# 74HC595.net
KiCad netlist of a schematic drawn in Altium Designer
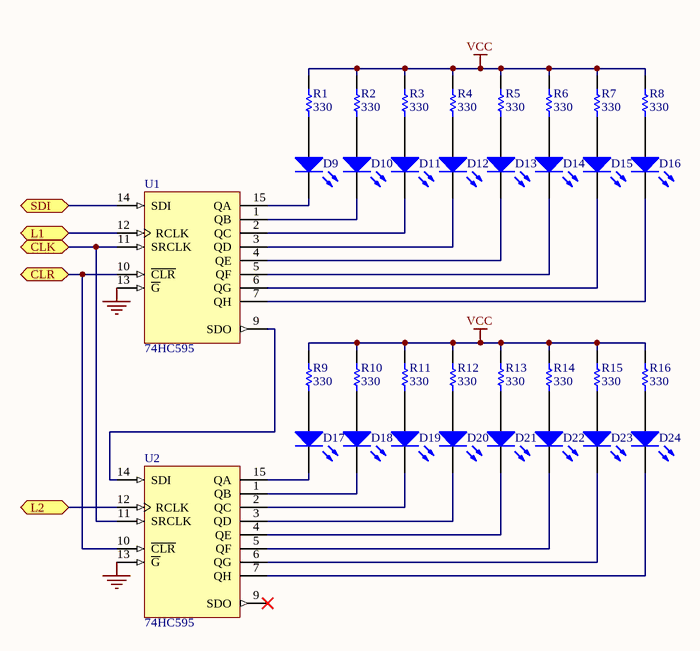
[diagram p0: 74HC595.SchDoc]

(export (version "E")
  (design (tool "Eeschema 10.0.6"))
  (components
    (comp (ref "D9")
      (value "LED0")
      (footprint "CAPPR2-5X6.8")
      (description "Typical INFRARED GaAs LED")
      (fields (field (name "PUBLISHER") "Altium Limited"))
      (libsource (lib "Miscellaneous Devices") (part "LED0"))
    )
    (comp (ref "D10")
      (value "LED0")
      (footprint "CAPPR2-5X6.8")
      (description "Typical INFRARED GaAs LED")
      (fields (field (name "PUBLISHER") "Altium Limited"))
      (libsource (lib "Miscellaneous Devices") (part "LED0"))
    )
    (comp (ref "D11")
      (value "LED0")
      (footprint "CAPPR2-5X6.8")
      (description "Typical INFRARED GaAs LED")
      (fields (field (name "PUBLISHER") "Altium Limited"))
      (libsource (lib "Miscellaneous Devices") (part "LED0"))
    )
    (comp (ref "D12")
      (value "LED0")
      (footprint "CAPPR2-5X6.8")
      (description "Typical INFRARED GaAs LED")
      (fields (field (name "PUBLISHER") "Altium Limited"))
      (libsource (lib "Miscellaneous Devices") (part "LED0"))
    )
    (comp (ref "D13")
      (value "LED0")
      (footprint "CAPPR2-5X6.8")
      (description "Typical INFRARED GaAs LED")
      (fields (field (name "PUBLISHER") "Altium Limited"))
      (libsource (lib "Miscellaneous Devices") (part "LED0"))
    )
    (comp (ref "D14")
      (value "LED0")
      (footprint "CAPPR2-5X6.8")
      (description "Typical INFRARED GaAs LED")
      (fields (field (name "PUBLISHER") "Altium Limited"))
      (libsource (lib "Miscellaneous Devices") (part "LED0"))
    )
    (comp (ref "D15")
      (value "LED0")
      (footprint "CAPPR2-5X6.8")
      (description "Typical INFRARED GaAs LED")
      (fields (field (name "PUBLISHER") "Altium Limited"))
      (libsource (lib "Miscellaneous Devices") (part "LED0"))
    )
    (comp (ref "D16")
      (value "LED0")
      (footprint "CAPPR2-5X6.8")
      (description "Typical INFRARED GaAs LED")
      (fields (field (name "PUBLISHER") "Altium Limited"))
      (libsource (lib "Miscellaneous Devices") (part "LED0"))
    )
    (comp (ref "D17")
      (value "LED0")
      (footprint "CAPPR2-5X6.8")
      (description "Typical INFRARED GaAs LED")
      (fields (field (name "PUBLISHER") "Altium Limited"))
      (libsource (lib "Miscellaneous Devices") (part "LED0"))
    )
    (comp (ref "D18")
      (value "LED0")
      (footprint "CAPPR2-5X6.8")
      (description "Typical INFRARED GaAs LED")
      (fields (field (name "PUBLISHER") "Altium Limited"))
      (libsource (lib "Miscellaneous Devices") (part "LED0"))
    )
    (comp (ref "D19")
      (value "LED0")
      (footprint "CAPPR2-5X6.8")
      (description "Typical INFRARED GaAs LED")
      (fields (field (name "PUBLISHER") "Altium Limited"))
      (libsource (lib "Miscellaneous Devices") (part "LED0"))
    )
    (comp (ref "D20")
      (value "LED0")
      (footprint "CAPPR2-5X6.8")
      (description "Typical INFRARED GaAs LED")
      (fields (field (name "PUBLISHER") "Altium Limited"))
      (libsource (lib "Miscellaneous Devices") (part "LED0"))
    )
    (comp (ref "D21")
      (value "LED0")
      (footprint "CAPPR2-5X6.8")
      (description "Typical INFRARED GaAs LED")
      (fields (field (name "PUBLISHER") "Altium Limited"))
      (libsource (lib "Miscellaneous Devices") (part "LED0"))
    )
    (comp (ref "D22")
      (value "LED0")
      (footprint "CAPPR2-5X6.8")
      (description "Typical INFRARED GaAs LED")
      (fields (field (name "PUBLISHER") "Altium Limited"))
      (libsource (lib "Miscellaneous Devices") (part "LED0"))
    )
    (comp (ref "D23")
      (value "LED0")
      (footprint "CAPPR2-5X6.8")
      (description "Typical INFRARED GaAs LED")
      (fields (field (name "PUBLISHER") "Altium Limited"))
      (libsource (lib "Miscellaneous Devices") (part "LED0"))
    )
    (comp (ref "D24")
      (value "LED0")
      (footprint "CAPPR2-5X6.8")
      (description "Typical INFRARED GaAs LED")
      (fields (field (name "PUBLISHER") "Altium Limited"))
      (libsource (lib "Miscellaneous Devices") (part "LED0"))
    )
    (comp (ref "R1")
      (value "330")
      (footprint "CAPC2012L")
      (description "Resistor")
      (fields (field (name "PUBLISHER") "Altium Limited"))
      (libsource (lib "Miscellaneous Devices") (part "Res1"))
    )
    (comp (ref "R2")
      (value "330")
      (footprint "CAPC2012L")
      (description "Resistor")
      (fields (field (name "PUBLISHER") "Altium Limited"))
      (libsource (lib "Miscellaneous Devices") (part "Res1"))
    )
    (comp (ref "R3")
      (value "330")
      (footprint "CAPC2012L")
      (description "Resistor")
      (fields (field (name "PUBLISHER") "Altium Limited"))
      (libsource (lib "Miscellaneous Devices") (part "Res1"))
    )
    (comp (ref "R4")
      (value "330")
      (footprint "CAPC2012L")
      (description "Resistor")
      (fields (field (name "PUBLISHER") "Altium Limited"))
      (libsource (lib "Miscellaneous Devices") (part "Res1"))
    )
    (comp (ref "R5")
      (value "330")
      (footprint "CAPC2012L")
      (description "Resistor")
      (fields (field (name "PUBLISHER") "Altium Limited"))
      (libsource (lib "Miscellaneous Devices") (part "Res1"))
    )
    (comp (ref "R6")
      (value "330")
      (footprint "CAPC2012L")
      (description "Resistor")
      (fields (field (name "PUBLISHER") "Altium Limited"))
      (libsource (lib "Miscellaneous Devices") (part "Res1"))
    )
    (comp (ref "R7")
      (value "330")
      (footprint "CAPC2012L")
      (description "Resistor")
      (fields (field (name "PUBLISHER") "Altium Limited"))
      (libsource (lib "Miscellaneous Devices") (part "Res1"))
    )
    (comp (ref "R8")
      (value "330")
      (footprint "CAPC2012L")
      (description "Resistor")
      (fields (field (name "PUBLISHER") "Altium Limited"))
      (libsource (lib "Miscellaneous Devices") (part "Res1"))
    )
    (comp (ref "R9")
      (value "330")
      (footprint "CAPC2012L")
      (description "Resistor")
      (fields (field (name "PUBLISHER") "Altium Limited"))
      (libsource (lib "Miscellaneous Devices") (part "Res1"))
    )
    (comp (ref "R10")
      (value "330")
      (footprint "CAPC2012L")
      (description "Resistor")
      (fields (field (name "PUBLISHER") "Altium Limited"))
      (libsource (lib "Miscellaneous Devices") (part "Res1"))
    )
    (comp (ref "R11")
      (value "330")
      (footprint "CAPC2012L")
      (description "Resistor")
      (fields (field (name "PUBLISHER") "Altium Limited"))
      (libsource (lib "Miscellaneous Devices") (part "Res1"))
    )
    (comp (ref "R12")
      (value "330")
      (footprint "CAPC2012L")
      (description "Resistor")
      (fields (field (name "PUBLISHER") "Altium Limited"))
      (libsource (lib "Miscellaneous Devices") (part "Res1"))
    )
    (comp (ref "R13")
      (value "330")
      (footprint "CAPC2012L")
      (description "Resistor")
      (fields (field (name "PUBLISHER") "Altium Limited"))
      (libsource (lib "Miscellaneous Devices") (part "Res1"))
    )
    (comp (ref "R14")
      (value "330")
      (footprint "CAPC2012L")
      (description "Resistor")
      (fields (field (name "PUBLISHER") "Altium Limited"))
      (libsource (lib "Miscellaneous Devices") (part "Res1"))
    )
    (comp (ref "R15")
      (value "330")
      (footprint "CAPC2012L")
      (description "Resistor")
      (fields (field (name "PUBLISHER") "Altium Limited"))
      (libsource (lib "Miscellaneous Devices") (part "Res1"))
    )
    (comp (ref "R16")
      (value "330")
      (footprint "CAPC2012L")
      (description "Resistor")
      (fields (field (name "PUBLISHER") "Altium Limited"))
      (libsource (lib "Miscellaneous Devices") (part "Res1"))
    )
    (comp (ref "U1")
      (value "74HC595")
      (footprint "DIP16")
      (description "8 Bit Shift Register with Output Latches (3 STATE)")
      (fields (field (name "PUBLISHER") "Altium Limited"))
      (libsource (lib "PCB_Project1") (part "M74HC595B1R"))
    )
    (comp (ref "U2")
      (value "74HC595")
      (footprint "DIP16")
      (description "8 Bit Shift Register with Output Latches (3 STATE)")
      (fields (field (name "PUBLISHER") "Altium Limited"))
      (libsource (lib "PCB_Project1") (part "M74HC595B1R"))
    )
  )
  (nets
    (net (code "1") (name "/CLK") (class "Default")
      (node (ref "U1") (pin "11") (pinfunction "SRCLK_11") (pintype "input"))
      (node (ref "U2") (pin "11") (pinfunction "SRCLK_11") (pintype "input"))
    )
    (net (code "2") (name "/CLR") (class "Default")
      (node (ref "U1") (pin "10") (pinfunction "~{CLR}_10") (pintype "input"))
      (node (ref "U2") (pin "10") (pinfunction "~{CLR}_10") (pintype "input"))
    )
    (net (code "3") (name "/L1") (class "Default")
      (node (ref "U1") (pin "12") (pinfunction "RCLK_12") (pintype "input"))
    )
    (net (code "4") (name "/L2") (class "Default")
      (node (ref "U2") (pin "12") (pinfunction "RCLK_12") (pintype "input"))
    )
    (net (code "5") (name "/SDI") (class "Default")
      (node (ref "U1") (pin "14") (pinfunction "SDI_14") (pintype "input"))
    )
    (net (code "6") (name "GND") (class "Default")
      (node (ref "U1") (pin "13") (pinfunction "~{G}_13") (pintype "input"))
      (node (ref "U1") (pin "8") (pinfunction "GND_8") (pintype "power_in"))
      (node (ref "U2") (pin "13") (pinfunction "~{G}_13") (pintype "input"))
      (node (ref "U2") (pin "8") (pinfunction "GND_8") (pintype "power_in"))
    )
    (net (code "7") (name "Net-(D9-A)") (class "Default")
      (node (ref "D9") (pin "1") (pinfunction "A_1") (pintype "passive"))
      (node (ref "R1") (pin "1") (pinfunction "1_1") (pintype "passive"))
    )
    (net (code "8") (name "Net-(D9-K)") (class "Default")
      (node (ref "D9") (pin "2") (pinfunction "K_2") (pintype "passive"))
      (node (ref "U1") (pin "15") (pinfunction "QA_15") (pintype "tri_state"))
    )
    (net (code "9") (name "Net-(D10-A)") (class "Default")
      (node (ref "D10") (pin "1") (pinfunction "A_1") (pintype "passive"))
      (node (ref "R2") (pin "1") (pinfunction "1_1") (pintype "passive"))
    )
    (net (code "10") (name "Net-(D10-K)") (class "Default")
      (node (ref "D10") (pin "2") (pinfunction "K_2") (pintype "passive"))
      (node (ref "U1") (pin "1") (pinfunction "QB_1") (pintype "tri_state"))
    )
    (net (code "11") (name "Net-(D11-A)") (class "Default")
      (node (ref "D11") (pin "1") (pinfunction "A_1") (pintype "passive"))
      (node (ref "R3") (pin "1") (pinfunction "1_1") (pintype "passive"))
    )
    (net (code "12") (name "Net-(D11-K)") (class "Default")
      (node (ref "D11") (pin "2") (pinfunction "K_2") (pintype "passive"))
      (node (ref "U1") (pin "2") (pinfunction "QC_2") (pintype "tri_state"))
    )
    (net (code "13") (name "Net-(D12-A)") (class "Default")
      (node (ref "D12") (pin "1") (pinfunction "A_1") (pintype "passive"))
      (node (ref "R4") (pin "1") (pinfunction "1_1") (pintype "passive"))
    )
    (net (code "14") (name "Net-(D12-K)") (class "Default")
      (node (ref "D12") (pin "2") (pinfunction "K_2") (pintype "passive"))
      (node (ref "U1") (pin "3") (pinfunction "QD_3") (pintype "tri_state"))
    )
    (net (code "15") (name "Net-(D13-A)") (class "Default")
      (node (ref "D13") (pin "1") (pinfunction "A_1") (pintype "passive"))
      (node (ref "R5") (pin "1") (pinfunction "1_1") (pintype "passive"))
    )
    (net (code "16") (name "Net-(D13-K)") (class "Default")
      (node (ref "D13") (pin "2") (pinfunction "K_2") (pintype "passive"))
      (node (ref "U1") (pin "4") (pinfunction "QE_4") (pintype "tri_state"))
    )
    (net (code "17") (name "Net-(D14-A)") (class "Default")
      (node (ref "D14") (pin "1") (pinfunction "A_1") (pintype "passive"))
      (node (ref "R6") (pin "1") (pinfunction "1_1") (pintype "passive"))
    )
    (net (code "18") (name "Net-(D14-K)") (class "Default")
      (node (ref "D14") (pin "2") (pinfunction "K_2") (pintype "passive"))
      (node (ref "U1") (pin "5") (pinfunction "QF_5") (pintype "tri_state"))
    )
    (net (code "19") (name "Net-(D15-A)") (class "Default")
      (node (ref "D15") (pin "1") (pinfunction "A_1") (pintype "passive"))
      (node (ref "R7") (pin "1") (pinfunction "1_1") (pintype "passive"))
    )
    (net (code "20") (name "Net-(D15-K)") (class "Default")
      (node (ref "D15") (pin "2") (pinfunction "K_2") (pintype "passive"))
      (node (ref "U1") (pin "6") (pinfunction "QG_6") (pintype "tri_state"))
    )
    (net (code "21") (name "Net-(D16-A)") (class "Default")
      (node (ref "D16") (pin "1") (pinfunction "A_1") (pintype "passive"))
      (node (ref "R8") (pin "1") (pinfunction "1_1") (pintype "passive"))
    )
    (net (code "22") (name "Net-(D16-K)") (class "Default")
      (node (ref "D16") (pin "2") (pinfunction "K_2") (pintype "passive"))
      (node (ref "U1") (pin "7") (pinfunction "QH_7") (pintype "tri_state"))
    )
    (net (code "23") (name "Net-(D17-A)") (class "Default")
      (node (ref "D17") (pin "1") (pinfunction "A_1") (pintype "passive"))
      (node (ref "R9") (pin "1") (pinfunction "1_1") (pintype "passive"))
    )
    (net (code "24") (name "Net-(D17-K)") (class "Default")
      (node (ref "D17") (pin "2") (pinfunction "K_2") (pintype "passive"))
      (node (ref "U2") (pin "15") (pinfunction "QA_15") (pintype "tri_state"))
    )
    (net (code "25") (name "Net-(D18-A)") (class "Default")
      (node (ref "D18") (pin "1") (pinfunction "A_1") (pintype "passive"))
      (node (ref "R10") (pin "1") (pinfunction "1_1") (pintype "passive"))
    )
    (net (code "26") (name "Net-(D18-K)") (class "Default")
      (node (ref "D18") (pin "2") (pinfunction "K_2") (pintype "passive"))
      (node (ref "U2") (pin "1") (pinfunction "QB_1") (pintype "tri_state"))
    )
    (net (code "27") (name "Net-(D19-A)") (class "Default")
      (node (ref "D19") (pin "1") (pinfunction "A_1") (pintype "passive"))
      (node (ref "R11") (pin "1") (pinfunction "1_1") (pintype "passive"))
    )
    (net (code "28") (name "Net-(D19-K)") (class "Default")
      (node (ref "D19") (pin "2") (pinfunction "K_2") (pintype "passive"))
      (node (ref "U2") (pin "2") (pinfunction "QC_2") (pintype "tri_state"))
    )
    (net (code "29") (name "Net-(D20-A)") (class "Default")
      (node (ref "D20") (pin "1") (pinfunction "A_1") (pintype "passive"))
      (node (ref "R12") (pin "1") (pinfunction "1_1") (pintype "passive"))
    )
    (net (code "30") (name "Net-(D20-K)") (class "Default")
      (node (ref "D20") (pin "2") (pinfunction "K_2") (pintype "passive"))
      (node (ref "U2") (pin "3") (pinfunction "QD_3") (pintype "tri_state"))
    )
    (net (code "31") (name "Net-(D21-A)") (class "Default")
      (node (ref "D21") (pin "1") (pinfunction "A_1") (pintype "passive"))
      (node (ref "R13") (pin "1") (pinfunction "1_1") (pintype "passive"))
    )
    (net (code "32") (name "Net-(D21-K)") (class "Default")
      (node (ref "D21") (pin "2") (pinfunction "K_2") (pintype "passive"))
      (node (ref "U2") (pin "4") (pinfunction "QE_4") (pintype "tri_state"))
    )
    (net (code "33") (name "Net-(D22-A)") (class "Default")
      (node (ref "D22") (pin "1") (pinfunction "A_1") (pintype "passive"))
      (node (ref "R14") (pin "1") (pinfunction "1_1") (pintype "passive"))
    )
    (net (code "34") (name "Net-(D22-K)") (class "Default")
      (node (ref "D22") (pin "2") (pinfunction "K_2") (pintype "passive"))
      (node (ref "U2") (pin "5") (pinfunction "QF_5") (pintype "tri_state"))
    )
    (net (code "35") (name "Net-(D23-A)") (class "Default")
      (node (ref "D23") (pin "1") (pinfunction "A_1") (pintype "passive"))
      (node (ref "R15") (pin "1") (pinfunction "1_1") (pintype "passive"))
    )
    (net (code "36") (name "Net-(D23-K)") (class "Default")
      (node (ref "D23") (pin "2") (pinfunction "K_2") (pintype "passive"))
      (node (ref "U2") (pin "6") (pinfunction "QG_6") (pintype "tri_state"))
    )
    (net (code "37") (name "Net-(D24-A)") (class "Default")
      (node (ref "D24") (pin "1") (pinfunction "A_1") (pintype "passive"))
      (node (ref "R16") (pin "1") (pinfunction "1_1") (pintype "passive"))
    )
    (net (code "38") (name "Net-(D24-K)") (class "Default")
      (node (ref "D24") (pin "2") (pinfunction "K_2") (pintype "passive"))
      (node (ref "U2") (pin "7") (pinfunction "QH_7") (pintype "tri_state"))
    )
    (net (code "39") (name "Net-(U1-SDO)") (class "Default")
      (node (ref "U1") (pin "9") (pinfunction "SDO_9") (pintype "output"))
      (node (ref "U2") (pin "14") (pinfunction "SDI_14") (pintype "input"))
    )
    (net (code "40") (name "VCC") (class "Default")
      (node (ref "R1") (pin "2") (pinfunction "2_2") (pintype "passive"))
      (node (ref "R10") (pin "2") (pinfunction "2_2") (pintype "passive"))
      (node (ref "R11") (pin "2") (pinfunction "2_2") (pintype "passive"))
      (node (ref "R12") (pin "2") (pinfunction "2_2") (pintype "passive"))
      (node (ref "R13") (pin "2") (pinfunction "2_2") (pintype "passive"))
      (node (ref "R14") (pin "2") (pinfunction "2_2") (pintype "passive"))
      (node (ref "R15") (pin "2") (pinfunction "2_2") (pintype "passive"))
      (node (ref "R16") (pin "2") (pinfunction "2_2") (pintype "passive"))
      (node (ref "R2") (pin "2") (pinfunction "2_2") (pintype "passive"))
      (node (ref "R3") (pin "2") (pinfunction "2_2") (pintype "passive"))
      (node (ref "R4") (pin "2") (pinfunction "2_2") (pintype "passive"))
      (node (ref "R5") (pin "2") (pinfunction "2_2") (pintype "passive"))
      (node (ref "R6") (pin "2") (pinfunction "2_2") (pintype "passive"))
      (node (ref "R7") (pin "2") (pinfunction "2_2") (pintype "passive"))
      (node (ref "R8") (pin "2") (pinfunction "2_2") (pintype "passive"))
      (node (ref "R9") (pin "2") (pinfunction "2_2") (pintype "passive"))
      (node (ref "U1") (pin "16") (pinfunction "VCC_16") (pintype "power_in"))
      (node (ref "U2") (pin "16") (pinfunction "VCC_16") (pintype "power_in"))
    )
    (net (code "41") (name "unconnected-(U2-SDO-Pad9)") (class "Default")
      (node (ref "U2") (pin "9") (pinfunction "SDO_9") (pintype "output+no_connect"))
    )
  )
)
